# Circuit_Altium.net
KiCad netlist of a schematic drawn in Altium Designer
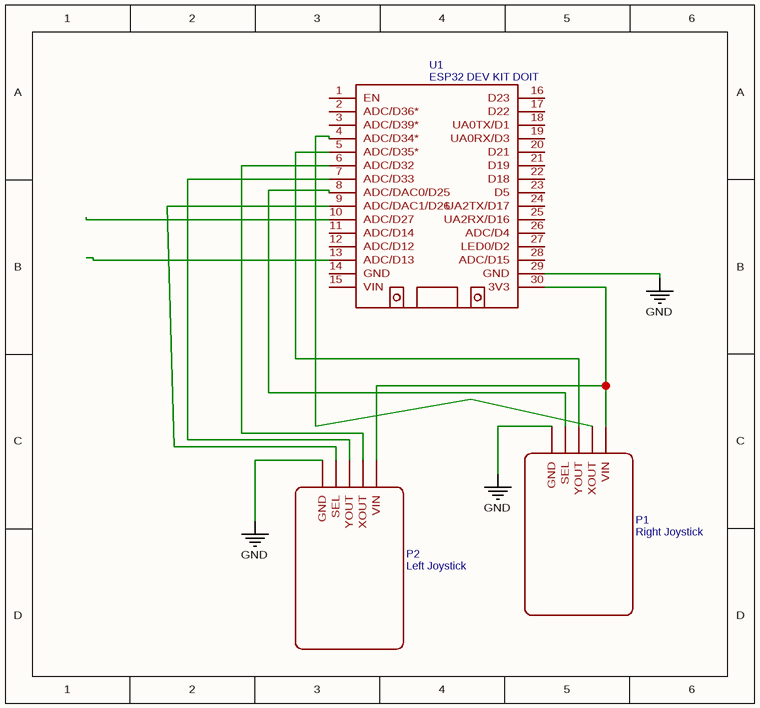
[diagram p0: Circuit_Altium.schdoc]

(export (version "E")
  (design (tool "Eeschema 10.0.6"))
  (components
    (comp (ref "P1")
      (value "Right Joystick")
      (libsource (lib "altium-import") (part "root_3_Right Joystick_"))
    )
    (comp (ref "P2") (value "Left Joystick") (libsource (lib "altium-import") (part "root_3_Left Joystick_")))
    (comp (ref "U1")
      (value "ESP32 DEV KIT DOIT")
      (fields (field (name "CONTRIBUTOR") "michael.garcia.h"))
      (libsource (lib "altium-import") (part "root_0_ESP32 DEV KIT DOIT_"))
    )
  )
  (nets
    (net (code "1") (name "GND") (class "Default")
      (node (ref "P1") (pin "GND") (pinfunction "GND_GND") (pintype "passive"))
      (node (ref "P2") (pin "GND") (pinfunction "GND_GND") (pintype "passive"))
      (node (ref "U1") (pin "29") (pinfunction "GND_29") (pintype "passive"))
    )
    (net (code "2") (name "Net-(P1-SEL)") (class "Default")
      (node (ref "P1") (pin "Key") (pinfunction "SEL_Key") (pintype "passive"))
      (node (ref "U1") (pin "8") (pinfunction "ADC/DAC0/D25_8") (pintype "passive"))
    )
    (net (code "3") (name "Net-(P1-VIN)") (class "Default")
      (node (ref "P1") (pin "VCC") (pinfunction "VIN_VCC") (pintype "passive"))
      (node (ref "P2") (pin "VCC") (pinfunction "VIN_VCC") (pintype "passive"))
      (node (ref "U1") (pin "30") (pinfunction "3V3_30") (pintype "passive"))
    )
    (net (code "4") (name "Net-(P2-SEL)") (class "Default")
      (node (ref "P2") (pin "Key") (pinfunction "SEL_Key") (pintype "passive"))
      (node (ref "U1") (pin "9") (pinfunction "ADC/DAC1/D26_9") (pintype "passive"))
    )
    (net (code "5") (name "Net-(U1-ADC{slash}D32)") (class "Default")
      (node (ref "P2") (pin "XOUT") (pinfunction "XOUT_XOUT") (pintype "passive"))
      (node (ref "U1") (pin "6") (pinfunction "ADC/D32_6") (pintype "passive"))
    )
    (net (code "6") (name "Net-(U1-ADC{slash}D33)") (class "Default")
      (node (ref "P2") (pin "YOUT") (pinfunction "YOUT_YOUT") (pintype "passive"))
      (node (ref "U1") (pin "7") (pinfunction "ADC/D33_7") (pintype "passive"))
    )
    (net (code "7") (name "Net-(U1-ADC{slash}D34*)") (class "Default")
      (node (ref "P1") (pin "XOUT") (pinfunction "XOUT_XOUT") (pintype "passive"))
      (node (ref "U1") (pin "4") (pinfunction "ADC/D34*_4") (pintype "passive"))
    )
    (net (code "8") (name "Net-(U1-ADC{slash}D35*)") (class "Default")
      (node (ref "P1") (pin "YOUT") (pinfunction "YOUT_YOUT") (pintype "passive"))
      (node (ref "U1") (pin "5") (pinfunction "ADC/D35*_5") (pintype "passive"))
    )
    (net (code "9") (name "unconnected-(U1-ADC{slash}D4-Pad26)") (class "Default")
      (node (ref "U1") (pin "26") (pinfunction "ADC/D4_26") (pintype "passive"))
    )
    (net (code "10") (name "unconnected-(U1-ADC{slash}D12-Pad12)") (class "Default")
      (node (ref "U1") (pin "12") (pinfunction "ADC/D12_12") (pintype "passive"))
    )
    (net (code "11") (name "unconnected-(U1-ADC{slash}D13-Pad13)") (class "Default")
      (node (ref "U1") (pin "13") (pinfunction "ADC/D13_13") (pintype "passive"))
    )
    (net (code "12") (name "unconnected-(U1-ADC{slash}D14-Pad11)") (class "Default")
      (node (ref "U1") (pin "11") (pinfunction "ADC/D14_11") (pintype "passive"))
    )
    (net (code "13") (name "unconnected-(U1-ADC{slash}D15-Pad28)") (class "Default")
      (node (ref "U1") (pin "28") (pinfunction "ADC/D15_28") (pintype "passive"))
    )
    (net (code "14") (name "unconnected-(U1-ADC{slash}D27-Pad10)") (class "Default")
      (node (ref "U1") (pin "10") (pinfunction "ADC/D27_10") (pintype "passive"))
    )
    (net (code "15") (name "unconnected-(U1-ADC{slash}D36*-Pad2)") (class "Default")
      (node (ref "U1") (pin "2") (pinfunction "ADC/D36*_2") (pintype "passive"))
    )
    (net (code "16") (name "unconnected-(U1-ADC{slash}D39*-Pad3)") (class "Default")
      (node (ref "U1") (pin "3") (pinfunction "ADC/D39*_3") (pintype "passive"))
    )
    (net (code "17") (name "unconnected-(U1-D5-Pad23)") (class "Default")
      (node (ref "U1") (pin "23") (pinfunction "D5_23") (pintype "passive"))
    )
    (net (code "18") (name "unconnected-(U1-D18-Pad22)") (class "Default")
      (node (ref "U1") (pin "22") (pinfunction "D18_22") (pintype "passive"))
    )
    (net (code "19") (name "unconnected-(U1-D19-Pad21)") (class "Default")
      (node (ref "U1") (pin "21") (pinfunction "D19_21") (pintype "passive"))
    )
    (net (code "20") (name "unconnected-(U1-D21-Pad20)") (class "Default")
      (node (ref "U1") (pin "20") (pinfunction "D21_20") (pintype "passive"))
    )
    (net (code "21") (name "unconnected-(U1-D22-Pad17)") (class "Default")
      (node (ref "U1") (pin "17") (pinfunction "D22_17") (pintype "passive"))
    )
    (net (code "22") (name "unconnected-(U1-D23-Pad16)") (class "Default")
      (node (ref "U1") (pin "16") (pinfunction "D23_16") (pintype "passive"))
    )
    (net (code "23") (name "unconnected-(U1-EN-Pad1)") (class "Default")
      (node (ref "U1") (pin "1") (pinfunction "EN_1") (pintype "passive"))
    )
    (net (code "24") (name "unconnected-(U1-GND-Pad14)") (class "Default")
      (node (ref "U1") (pin "14") (pinfunction "GND_14") (pintype "passive"))
    )
    (net (code "25") (name "unconnected-(U1-LED0{slash}D2-Pad27)") (class "Default")
      (node (ref "U1") (pin "27") (pinfunction "LED0/D2_27") (pintype "passive"))
    )
    (net (code "26") (name "unconnected-(U1-UA0RX{slash}D3-Pad19)") (class "Default")
      (node (ref "U1") (pin "19") (pinfunction "UA0RX/D3_19") (pintype "passive"))
    )
    (net (code "27") (name "unconnected-(U1-UA0TX{slash}D1-Pad18)") (class "Default")
      (node (ref "U1") (pin "18") (pinfunction "UA0TX/D1_18") (pintype "passive"))
    )
    (net (code "28") (name "unconnected-(U1-UA2RX{slash}D16-Pad25)") (class "Default")
      (node (ref "U1") (pin "25") (pinfunction "UA2RX/D16_25") (pintype "passive"))
    )
    (net (code "29") (name "unconnected-(U1-UA2TX{slash}D17-Pad24)") (class "Default")
      (node (ref "U1") (pin "24") (pinfunction "UA2TX/D17_24") (pintype "passive"))
    )
    (net (code "30") (name "unconnected-(U1-VIN-Pad15)") (class "Default")
      (node (ref "U1") (pin "15") (pinfunction "VIN_15") (pintype "passive"))
    )
  )
)
